# Quad_ESC_adapter.net
KiCad netlist of a schematic drawn in EAGLE
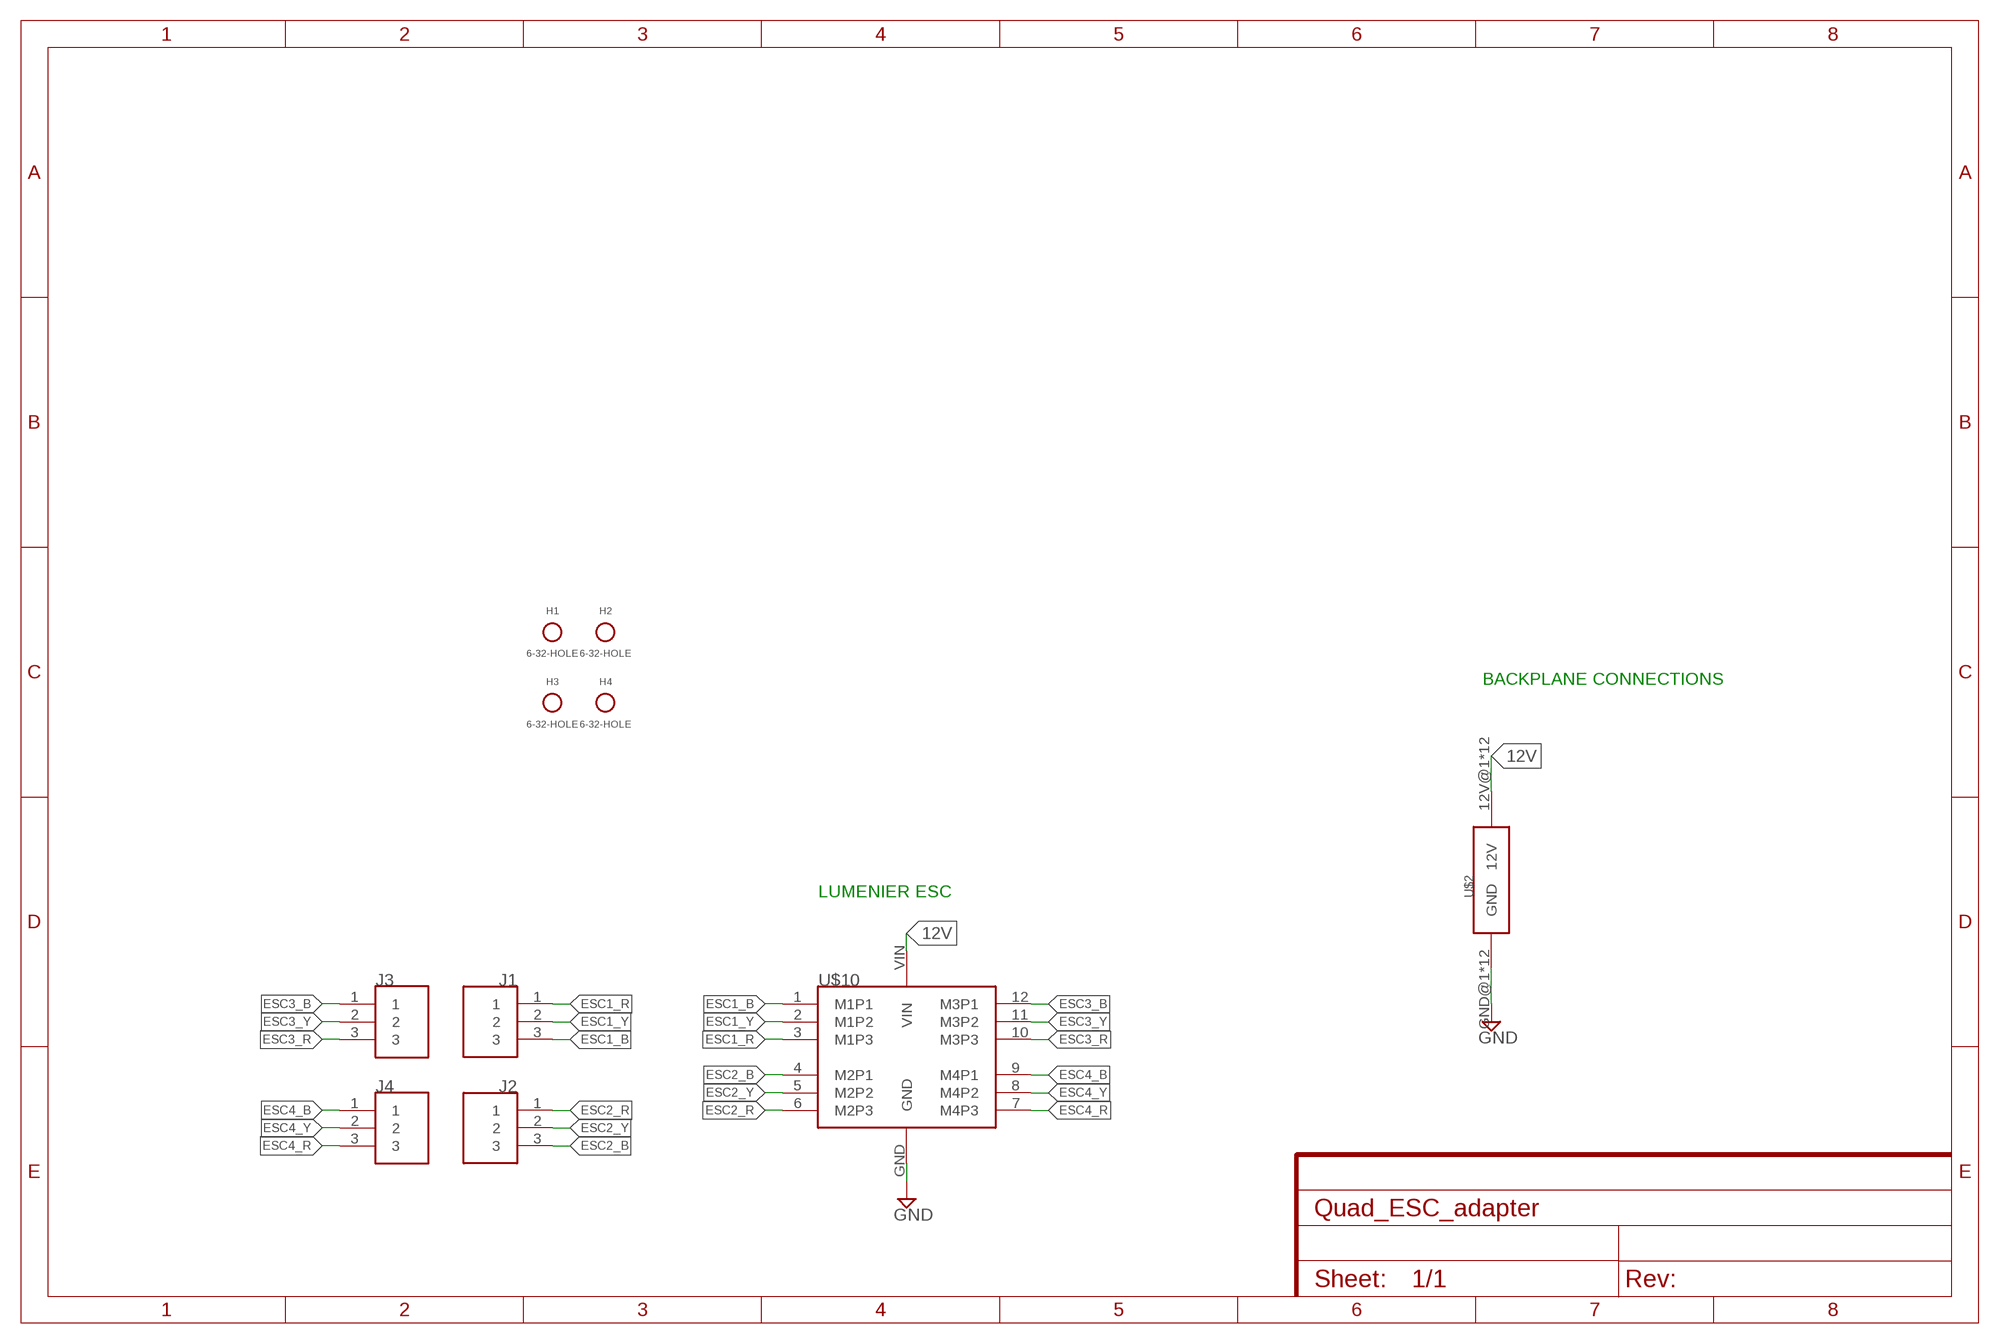
[diagram p0: schematic, sheet 1]

(export (version "E")
  (design (tool "Eeschema 10.0.6"))
  (components
    (comp (ref "H1")
      (value "6-32-HOLE")
      (footprint "eagle-import:6-32-HOLE")
      (libsource (lib "eagle-import") (part "6-32-HOLE"))
    )
    (comp (ref "H2")
      (value "6-32-HOLE")
      (footprint "eagle-import:6-32-HOLE")
      (libsource (lib "eagle-import") (part "6-32-HOLE"))
    )
    (comp (ref "H3")
      (value "6-32-HOLE")
      (footprint "eagle-import:6-32-HOLE")
      (libsource (lib "eagle-import") (part "6-32-HOLE"))
    )
    (comp (ref "H4")
      (value "6-32-HOLE")
      (footprint "eagle-import:6-32-HOLE")
      (libsource (lib "eagle-import") (part "6-32-HOLE"))
    )
    (comp (ref "J1")
      (value "IBPD-SOCKET")
      (footprint "eagle-import:IPBD-03-S-K")
      (libsource (lib "eagle-import") (part "IBPD-SOCKET"))
    )
    (comp (ref "J2")
      (value "IBPD-SOCKET")
      (footprint "eagle-import:IPBD-03-S-K")
      (libsource (lib "eagle-import") (part "IBPD-SOCKET"))
    )
    (comp (ref "J3")
      (value "IBPD-SOCKET")
      (footprint "eagle-import:IPBD-03-S-K")
      (libsource (lib "eagle-import") (part "IBPD-SOCKET"))
    )
    (comp (ref "J4")
      (value "IBPD-SOCKET")
      (footprint "eagle-import:IPBD-03-S-K")
      (libsource (lib "eagle-import") (part "IBPD-SOCKET"))
    )
    (comp (ref "U$2")
      (value "BACKPLANE_ESC_ADAPTER_PWRESC")
      (footprint "eagle-import:BACKPLANE_ESC_ADAPTER_ESC_PWR")
      (libsource (lib "eagle-import") (part "BACKPLANE_ESC_ADAPTER_PWRESC"))
    )
    (comp (ref "U$10")
      (value "LUMENIER_QUAD-NO-CUT")
      (footprint "eagle-import:LUMENIER_QUAD-NO-CUT")
      (libsource (lib "eagle-import") (part "LUMENIER_QUAD-NO-CUT"))
    )
  )
  (nets
    (net (code "1") (name "12V") (class "Default")
      (node (ref "U$10") (pin "VIN") (pinfunction "VIN_VIN") (pintype "bidirectional"))
      (node (ref "U$2") (pin "12V@1") (pinfunction "12V_12V@1") (pintype "bidirectional"))
      (node (ref "U$2") (pin "12V@10") (pinfunction "12V_12V@10") (pintype "bidirectional"))
      (node (ref "U$2") (pin "12V@11") (pinfunction "12V_12V@11") (pintype "bidirectional"))
      (node (ref "U$2") (pin "12V@12") (pinfunction "12V_12V@12") (pintype "bidirectional"))
      (node (ref "U$2") (pin "12V@2") (pinfunction "12V_12V@2") (pintype "bidirectional"))
      (node (ref "U$2") (pin "12V@3") (pinfunction "12V_12V@3") (pintype "bidirectional"))
      (node (ref "U$2") (pin "12V@4") (pinfunction "12V_12V@4") (pintype "bidirectional"))
      (node (ref "U$2") (pin "12V@5") (pinfunction "12V_12V@5") (pintype "bidirectional"))
      (node (ref "U$2") (pin "12V@6") (pinfunction "12V_12V@6") (pintype "bidirectional"))
      (node (ref "U$2") (pin "12V@7") (pinfunction "12V_12V@7") (pintype "bidirectional"))
      (node (ref "U$2") (pin "12V@8") (pinfunction "12V_12V@8") (pintype "bidirectional"))
      (node (ref "U$2") (pin "12V@9") (pinfunction "12V_12V@9") (pintype "bidirectional"))
    )
    (net (code "2") (name "ESC1_B") (class "Default")
      (node (ref "J1") (pin "3") (pinfunction "3_3") (pintype "bidirectional"))
      (node (ref "U$10") (pin "1") (pinfunction "M1P1_1") (pintype "bidirectional"))
    )
    (net (code "3") (name "ESC1_R") (class "Default")
      (node (ref "J1") (pin "1") (pinfunction "1_1") (pintype "bidirectional"))
      (node (ref "U$10") (pin "3") (pinfunction "M1P3_3") (pintype "bidirectional"))
    )
    (net (code "4") (name "ESC1_Y") (class "Default")
      (node (ref "J1") (pin "2") (pinfunction "2_2") (pintype "bidirectional"))
      (node (ref "U$10") (pin "2") (pinfunction "M1P2_2") (pintype "bidirectional"))
    )
    (net (code "5") (name "ESC2_B") (class "Default")
      (node (ref "J2") (pin "3") (pinfunction "3_3") (pintype "bidirectional"))
      (node (ref "U$10") (pin "4") (pinfunction "M2P1_4") (pintype "bidirectional"))
    )
    (net (code "6") (name "ESC2_R") (class "Default")
      (node (ref "J2") (pin "1") (pinfunction "1_1") (pintype "bidirectional"))
      (node (ref "U$10") (pin "6") (pinfunction "M2P3_6") (pintype "bidirectional"))
    )
    (net (code "7") (name "ESC2_Y") (class "Default")
      (node (ref "J2") (pin "2") (pinfunction "2_2") (pintype "bidirectional"))
      (node (ref "U$10") (pin "5") (pinfunction "M2P2_5") (pintype "bidirectional"))
    )
    (net (code "8") (name "ESC3_B") (class "Default")
      (node (ref "J3") (pin "1") (pinfunction "1_1") (pintype "bidirectional"))
      (node (ref "U$10") (pin "12") (pinfunction "M3P1_12") (pintype "bidirectional"))
    )
    (net (code "9") (name "ESC3_R") (class "Default")
      (node (ref "J3") (pin "3") (pinfunction "3_3") (pintype "bidirectional"))
      (node (ref "U$10") (pin "10") (pinfunction "M3P3_10") (pintype "bidirectional"))
    )
    (net (code "10") (name "ESC3_Y") (class "Default")
      (node (ref "J3") (pin "2") (pinfunction "2_2") (pintype "bidirectional"))
      (node (ref "U$10") (pin "11") (pinfunction "M3P2_11") (pintype "bidirectional"))
    )
    (net (code "11") (name "ESC4_B") (class "Default")
      (node (ref "J4") (pin "1") (pinfunction "1_1") (pintype "bidirectional"))
      (node (ref "U$10") (pin "9") (pinfunction "M4P1_9") (pintype "bidirectional"))
    )
    (net (code "12") (name "ESC4_R") (class "Default")
      (node (ref "J4") (pin "3") (pinfunction "3_3") (pintype "bidirectional"))
      (node (ref "U$10") (pin "7") (pinfunction "M4P3_7") (pintype "bidirectional"))
    )
    (net (code "13") (name "ESC4_Y") (class "Default")
      (node (ref "J4") (pin "2") (pinfunction "2_2") (pintype "bidirectional"))
      (node (ref "U$10") (pin "8") (pinfunction "M4P2_8") (pintype "bidirectional"))
    )
    (net (code "14") (name "GND") (class "Default")
      (node (ref "U$10") (pin "GND") (pinfunction "GND_GND") (pintype "bidirectional"))
      (node (ref "U$2") (pin "GND@1") (pinfunction "GND_GND@1") (pintype "bidirectional"))
      (node (ref "U$2") (pin "GND@10") (pinfunction "GND_GND@10") (pintype "bidirectional"))
      (node (ref "U$2") (pin "GND@11") (pinfunction "GND_GND@11") (pintype "bidirectional"))
      (node (ref "U$2") (pin "GND@12") (pinfunction "GND_GND@12") (pintype "bidirectional"))
      (node (ref "U$2") (pin "GND@2") (pinfunction "GND_GND@2") (pintype "bidirectional"))
      (node (ref "U$2") (pin "GND@3") (pinfunction "GND_GND@3") (pintype "bidirectional"))
      (node (ref "U$2") (pin "GND@4") (pinfunction "GND_GND@4") (pintype "bidirectional"))
      (node (ref "U$2") (pin "GND@5") (pinfunction "GND_GND@5") (pintype "bidirectional"))
      (node (ref "U$2") (pin "GND@6") (pinfunction "GND_GND@6") (pintype "bidirectional"))
      (node (ref "U$2") (pin "GND@7") (pinfunction "GND_GND@7") (pintype "bidirectional"))
      (node (ref "U$2") (pin "GND@8") (pinfunction "GND_GND@8") (pintype "bidirectional"))
      (node (ref "U$2") (pin "GND@9") (pinfunction "GND_GND@9") (pintype "bidirectional"))
    )
  )
)
